# RPL_POWER_5V.net
KiCad netlist of a schematic drawn in Altium Designer
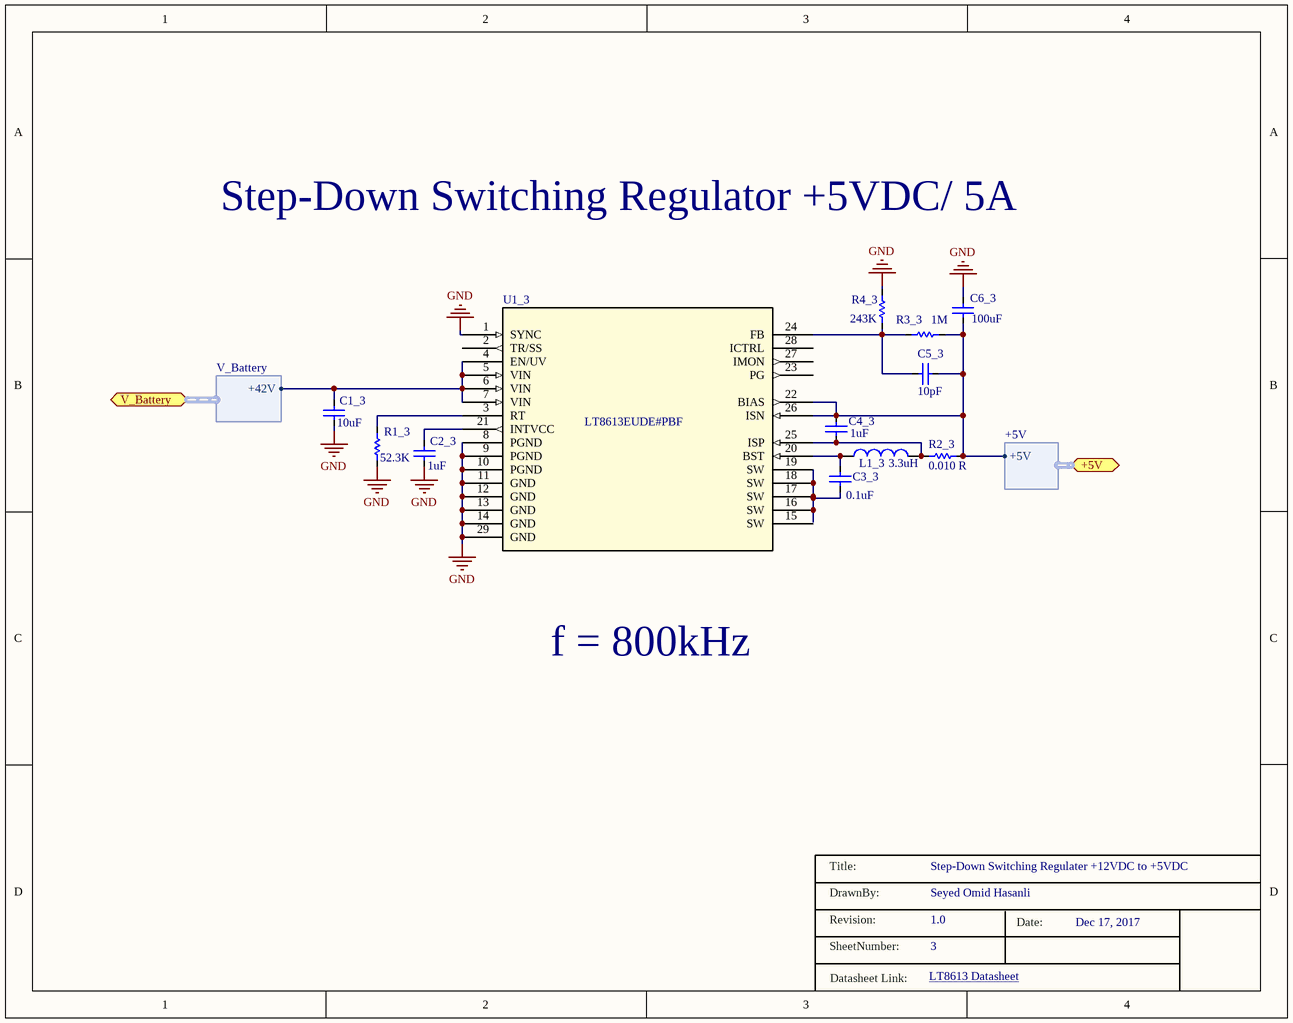
[diagram p0: RPL_POWER_5V.SchDoc]

(export (version "E")
  (design (tool "Eeschema 10.0.6"))
  (components
    (comp (ref "C1_3")
      (value "10uF")
      (footprint "C0805C475K9RACAUTO")
      (fields (field (name "Comment") "Cap"))
      (libsource (lib "Generic_Library") (part "Cap"))
    )
    (comp (ref "C2_3")
      (value "1uF")
      (footprint "C0805C475K9RACAUTO")
      (fields (field (name "Comment") "Cap"))
      (libsource (lib "Generic_Library") (part "Cap"))
    )
    (comp (ref "C3_3")
      (value "0.1uF")
      (footprint "C0805C475K9RACAUTO")
      (fields (field (name "Comment") "Cap"))
      (libsource (lib "Generic_Library") (part "Cap"))
    )
    (comp (ref "C4_3")
      (value "1uF")
      (footprint "C0805C475K9RACAUTO")
      (fields (field (name "Comment") "Cap"))
      (libsource (lib "Generic_Library") (part "Cap"))
    )
    (comp (ref "C5_3")
      (value "10pF")
      (footprint "C0805C475K9RACAUTO")
      (fields (field (name "Comment") "Cap"))
      (libsource (lib "Generic_Library") (part "Cap"))
    )
    (comp (ref "C6_3")
      (value "100uF")
      (footprint "C0805C475K9RACAUTO")
      (fields (field (name "Comment") "Cap"))
      (libsource (lib "Generic_Library") (part "Cap"))
    )
    (comp (ref "L1_3")
      (value "3.3uH")
      (footprint "IHLP2525EZER3R3M01")
      (fields (field (name "Comment") "VISHAY IHLP2525EZ-01"))
      (libsource (lib "Generic_Library") (part "Inductor"))
    )
    (comp (ref "R1_3")
      (value "52.3K")
      (footprint "SMD Resistors:RES 0805")
      (fields (field (name "Comment") "Res"))
      (libsource (lib "Generic_Library") (part "Res"))
    )
    (comp (ref "R2_3")
      (value "0.010 R")
      (footprint "SMD Resistors:RES 1206")
      (fields (field (name "Comment") "Res"))
      (libsource (lib "Generic_Library") (part "Res"))
    )
    (comp (ref "R3_3")
      (value "1M")
      (footprint "SMD Resistors:RES 0805")
      (fields (field (name "Comment") "Res"))
      (libsource (lib "Generic_Library") (part "Res"))
    )
    (comp (ref "R4_3")
      (value "243K")
      (footprint "SMD Resistors:RES 0805")
      (fields (field (name "Comment") "Res"))
      (libsource (lib "Generic_Library") (part "Res"))
    )
    (comp (ref "U1_3")
      (value "LT8613EUDE#PBF")
      (footprint "QFN-28_UDE-L")
      (description "Imported")
      (fields (field (name "MANUFACTURER_PART_NUMBER") "lt8613eude#pbf"))
      (libsource (lib "Generic_Library") (part "LT8613EUDE#PBF"))
    )
  )
  (nets
    (net (code "5") (name "GND") (class "Default")
      (node (ref "C1_3") (pin "1") (pinfunction "1_1") (pintype "passive"))
      (node (ref "C2_3") (pin "1") (pinfunction "1_1") (pintype "passive"))
      (node (ref "C6_3") (pin "2") (pinfunction "2_2") (pintype "passive"))
      (node (ref "R1_3") (pin "1") (pinfunction "1_1") (pintype "passive"))
      (node (ref "R4_3") (pin "2") (pinfunction "2_2") (pintype "passive"))
      (node (ref "U1_3") (pin "1") (pinfunction "SYNC_1") (pintype "input"))
      (node (ref "U1_3") (pin "10") (pinfunction "PGND_10") (pintype "power_in"))
      (node (ref "U1_3") (pin "11") (pinfunction "GND_11") (pintype "power_in"))
      (node (ref "U1_3") (pin "12") (pinfunction "GND_12") (pintype "power_in"))
      (node (ref "U1_3") (pin "13") (pinfunction "GND_13") (pintype "power_in"))
      (node (ref "U1_3") (pin "14") (pinfunction "GND_14") (pintype "power_in"))
      (node (ref "U1_3") (pin "29") (pinfunction "GND_29") (pintype "power_in"))
      (node (ref "U1_3") (pin "8") (pinfunction "PGND_8") (pintype "power_in"))
      (node (ref "U1_3") (pin "9") (pinfunction "PGND_9") (pintype "power_in"))
    )
    (net (code "6") (name "Net-(C3_3-Pad1)") (class "Default")
      (node (ref "C3_3") (pin "1") (pinfunction "1_1") (pintype "passive"))
      (node (ref "U1_3") (pin "16") (pinfunction "SW_16") (pintype "passive"))
      (node (ref "U1_3") (pin "17") (pinfunction "SW_17") (pintype "passive"))
      (node (ref "U1_3") (pin "18") (pinfunction "SW_18") (pintype "passive"))
      (node (ref "U1_3") (pin "19") (pinfunction "SW_19") (pintype "passive"))
    )
    (net (code "7") (name "Net-(U1_3-BIAS)") (class "Default")
      (node (ref "C4_3") (pin "1") (pinfunction "1_1") (pintype "passive"))
      (node (ref "C5_3") (pin "1") (pinfunction "1_1") (pintype "passive"))
      (node (ref "C6_3") (pin "1") (pinfunction "1_1") (pintype "passive"))
      (node (ref "R2_3") (pin "2") (pinfunction "2_2") (pintype "passive"))
      (node (ref "R3_3") (pin "2") (pinfunction "2_2") (pintype "passive"))
      (node (ref "U1_3") (pin "22") (pinfunction "BIAS_22") (pintype "output"))
      (node (ref "U1_3") (pin "26") (pinfunction "ISN_26") (pintype "input"))
    )
    (net (code "8") (name "Net-(U1_3-BST)") (class "Default")
      (node (ref "C3_3") (pin "2") (pinfunction "2_2") (pintype "passive"))
      (node (ref "L1_3") (pin "1") (pinfunction "1_1") (pintype "passive"))
      (node (ref "U1_3") (pin "20") (pinfunction "BST_20") (pintype "input"))
    )
    (net (code "9") (name "Net-(U1_3-EN{slash}UV)") (class "Default")
      (node (ref "C1_3") (pin "2") (pinfunction "2_2") (pintype "passive"))
      (node (ref "U1_3") (pin "4") (pinfunction "EN/UV_4") (pintype "passive"))
      (node (ref "U1_3") (pin "5") (pinfunction "VIN_5") (pintype "input"))
      (node (ref "U1_3") (pin "6") (pinfunction "VIN_6") (pintype "input"))
      (node (ref "U1_3") (pin "7") (pinfunction "VIN_7") (pintype "input"))
    )
    (net (code "10") (name "Net-(U1_3-FB)") (class "Default")
      (node (ref "C5_3") (pin "2") (pinfunction "2_2") (pintype "passive"))
      (node (ref "R3_3") (pin "1") (pinfunction "1_1") (pintype "passive"))
      (node (ref "R4_3") (pin "1") (pinfunction "1_1") (pintype "passive"))
      (node (ref "U1_3") (pin "24") (pinfunction "FB_24") (pintype "passive"))
    )
    (net (code "11") (name "Net-(U1_3-INTVCC)") (class "Default")
      (node (ref "C2_3") (pin "2") (pinfunction "2_2") (pintype "passive"))
      (node (ref "U1_3") (pin "21") (pinfunction "INTVCC_21") (pintype "output"))
    )
    (net (code "12") (name "Net-(U1_3-ISP)") (class "Default")
      (node (ref "C4_3") (pin "2") (pinfunction "2_2") (pintype "passive"))
      (node (ref "L1_3") (pin "2") (pinfunction "2_2") (pintype "passive"))
      (node (ref "R2_3") (pin "1") (pinfunction "1_1") (pintype "passive"))
      (node (ref "U1_3") (pin "25") (pinfunction "ISP_25") (pintype "input"))
    )
    (net (code "13") (name "Net-(U1_3-RT)") (class "Default")
      (node (ref "R1_3") (pin "2") (pinfunction "2_2") (pintype "passive"))
      (node (ref "U1_3") (pin "3") (pinfunction "RT_3") (pintype "passive"))
    )
    (net (code "14") (name "unconnected-(U1_3-ICTRL-Pad28)") (class "Default")
      (node (ref "U1_3") (pin "28") (pinfunction "ICTRL_28") (pintype "passive"))
    )
    (net (code "15") (name "unconnected-(U1_3-IMON-Pad27)") (class "Default")
      (node (ref "U1_3") (pin "27") (pinfunction "IMON_27") (pintype "output"))
    )
    (net (code "16") (name "unconnected-(U1_3-PG-Pad23)") (class "Default")
      (node (ref "U1_3") (pin "23") (pinfunction "PG_23") (pintype "output"))
    )
    (net (code "17") (name "unconnected-(U1_3-SW-Pad15)") (class "Default")
      (node (ref "U1_3") (pin "15") (pinfunction "SW_15") (pintype "passive"))
    )
    (net (code "18") (name "unconnected-(U1_3-TR{slash}SS-Pad2)") (class "Default")
      (node (ref "U1_3") (pin "2") (pinfunction "TR/SS_2") (pintype "output"))
    )
  )
)
